# 03_ENET.net
KiCad netlist of a schematic drawn in Altium Designer
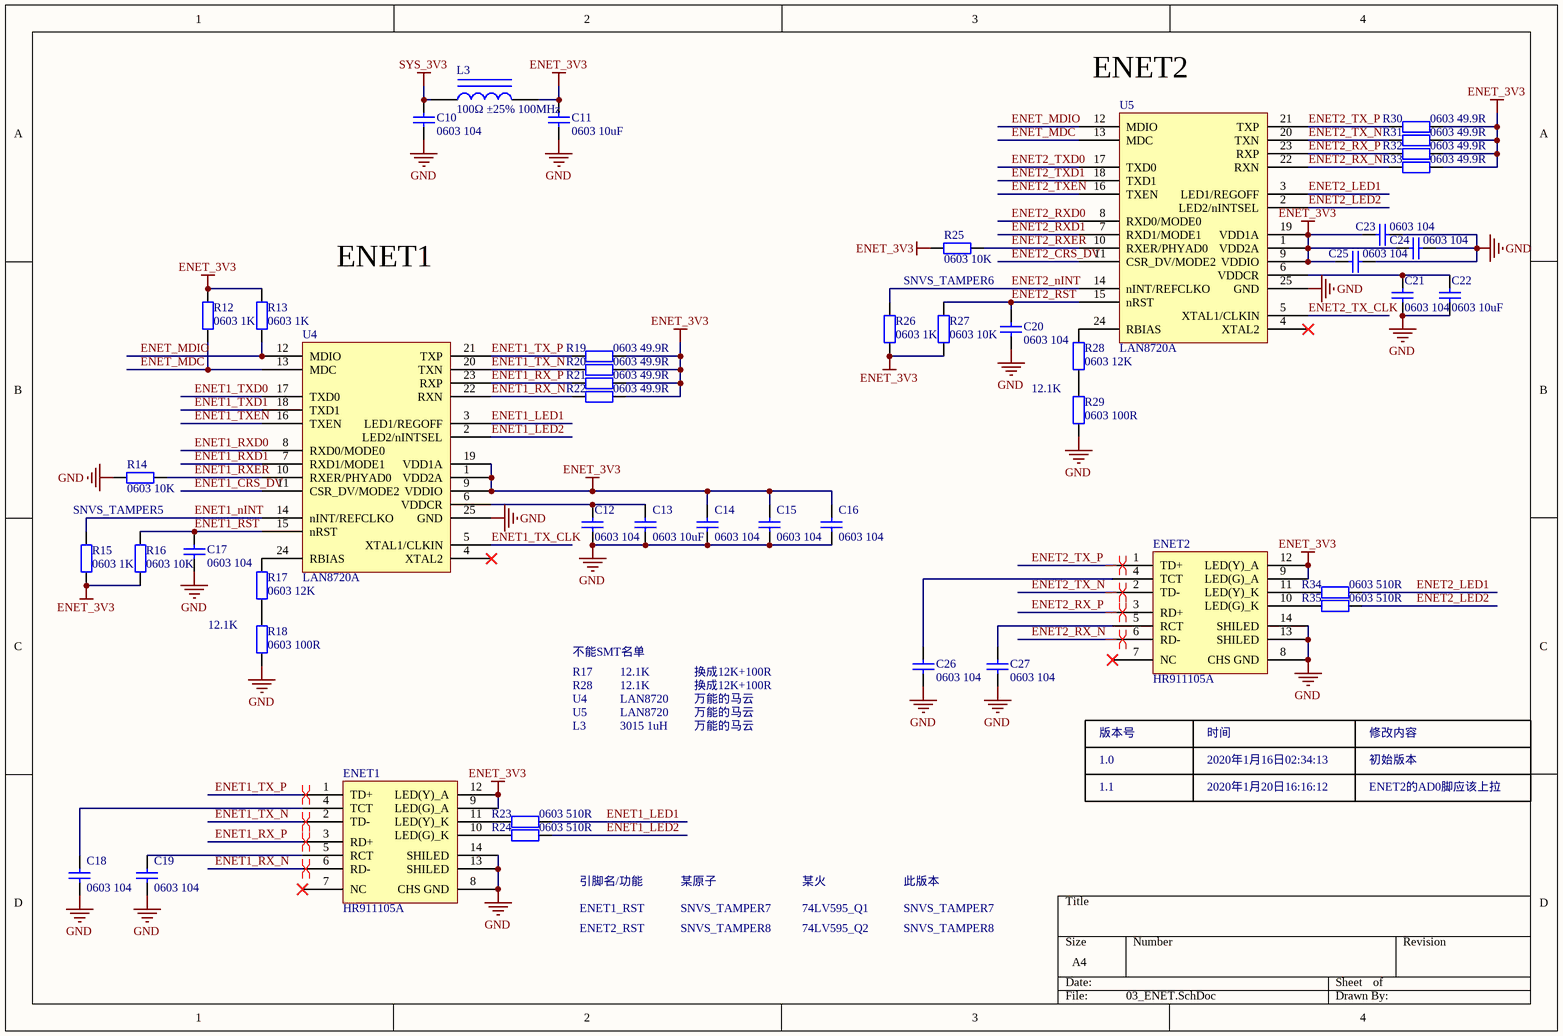
[diagram p0: 03_ENET.SchDoc]

(export (version "E")
  (design (tool "Eeschema 10.0.6"))
  (components
    (comp (ref "C10")
      (value "0603 104")
      (footprint "LC-0603_C")
      (description "贴片电容")
      (libsource (lib "JLC") (part "0603 1.5nF (152) 10% 50V"))
    )
    (comp (ref "C11")
      (value "0603 10uF")
      (footprint "LC-0603_C")
      (description "贴片电容")
      (libsource (lib "JLC") (part "0603 1.5nF (152) 10% 50V"))
    )
    (comp (ref "C12")
      (value "0603 104")
      (footprint "LC-0603_C")
      (description "贴片电容")
      (libsource (lib "JLC") (part "0603 1.5nF (152) 10% 50V"))
    )
    (comp (ref "C13")
      (value "0603 10uF")
      (footprint "LC-0603_C")
      (description "贴片电容")
      (libsource (lib "JLC") (part "0603 1.5nF (152) 10% 50V"))
    )
    (comp (ref "C14")
      (value "0603 104")
      (footprint "LC-0603_C")
      (description "贴片电容")
      (libsource (lib "JLC") (part "0603 1.5nF (152) 10% 50V"))
    )
    (comp (ref "C15")
      (value "0603 104")
      (footprint "LC-0603_C")
      (description "贴片电容")
      (libsource (lib "JLC") (part "0603 1.5nF (152) 10% 50V"))
    )
    (comp (ref "C16")
      (value "0603 104")
      (footprint "LC-0603_C")
      (description "贴片电容")
      (libsource (lib "JLC") (part "0603 1.5nF (152) 10% 50V"))
    )
    (comp (ref "C17")
      (value "0603 104")
      (footprint "LC-0603_C")
      (description "贴片电容")
      (libsource (lib "JLC") (part "0603 1.5nF (152) 10% 50V"))
    )
    (comp (ref "C18")
      (value "0603 104")
      (footprint "LC-0603_C")
      (description "贴片电容")
      (libsource (lib "JLC") (part "0603 1.5nF (152) 10% 50V"))
    )
    (comp (ref "C19")
      (value "0603 104")
      (footprint "LC-0603_C")
      (description "贴片电容")
      (libsource (lib "JLC") (part "0603 1.5nF (152) 10% 50V"))
    )
    (comp (ref "C20")
      (value "0603 104")
      (footprint "LC-0603_C")
      (description "贴片电容")
      (libsource (lib "JLC") (part "0603 1.5nF (152) 10% 50V"))
    )
    (comp (ref "C21")
      (value "0603 104")
      (footprint "LC-0603_C")
      (description "贴片电容")
      (libsource (lib "JLC") (part "0603 1.5nF (152) 10% 50V"))
    )
    (comp (ref "C22")
      (value "0603 10uF")
      (footprint "LC-0603_C")
      (description "贴片电容")
      (libsource (lib "JLC") (part "0603 1.5nF (152) 10% 50V"))
    )
    (comp (ref "C23")
      (value "0603 104")
      (footprint "LC-0603_C")
      (description "贴片电容")
      (libsource (lib "JLC") (part "0603 1.5nF (152) 10% 50V"))
    )
    (comp (ref "C24")
      (value "0603 104")
      (footprint "LC-0603_C")
      (description "贴片电容")
      (libsource (lib "JLC") (part "0603 1.5nF (152) 10% 50V"))
    )
    (comp (ref "C25")
      (value "0603 104")
      (footprint "LC-0603_C")
      (description "贴片电容")
      (libsource (lib "JLC") (part "0603 1.5nF (152) 10% 50V"))
    )
    (comp (ref "C26")
      (value "0603 104")
      (footprint "LC-0603_C")
      (description "贴片电容")
      (libsource (lib "JLC") (part "0603 1.5nF (152) 10% 50V"))
    )
    (comp (ref "C27")
      (value "0603 104")
      (footprint "LC-0603_C")
      (description "贴片电容")
      (libsource (lib "JLC") (part "0603 1.5nF (152) 10% 50V"))
    )
    (comp (ref "ENET1")
      (value "HR911105A")
      (footprint "HR911105A")
      (libsource (lib "Integrated_Library2") (part "HR911105A"))
    )
    (comp (ref "ENET2")
      (value "HR911105A")
      (footprint "HR911105A")
      (libsource (lib "Integrated_Library2") (part "HR911105A"))
    )
    (comp (ref "L3")
      (value "100Ω ±25% 100MHz")
      (footprint "LC-0805_L")
      (description "贴片磁珠")
      (libsource (lib "JLC") (part "0805 100Ω 25% 100MHz"))
    )
    (comp (ref "R12")
      (value "0603 1K")
      (footprint "LC-0603_R")
      (description "贴片电阻")
      (libsource (lib "") (part "0603 1.1KΩ (1101) 1%_1"))
    )
    (comp (ref "R13")
      (value "0603 1K")
      (footprint "LC-0603_R")
      (description "贴片电阻")
      (libsource (lib "") (part "0603 1.1KΩ (1101) 1%_1"))
    )
    (comp (ref "R14")
      (value "0603 10K")
      (footprint "LC-0603_R")
      (description "贴片电阻")
      (libsource (lib "JLC") (part "0603 1.1KΩ (1101) 1%"))
    )
    (comp (ref "R15")
      (value "0603 1K")
      (footprint "LC-0603_R")
      (description "贴片电阻")
      (libsource (lib "") (part "0603 1.1KΩ (1101) 1%_3"))
    )
    (comp (ref "R16")
      (value "0603 10K")
      (footprint "LC-0603_R")
      (description "贴片电阻")
      (libsource (lib "") (part "0603 1.1KΩ (1101) 1%_3"))
    )
    (comp (ref "R17")
      (value "0603 12K")
      (footprint "LC-0603_R")
      (description "贴片电阻")
      (libsource (lib "") (part "0603 1.1KΩ (1101) 1%_3"))
    )
    (comp (ref "R18")
      (value "0603 100R")
      (footprint "LC-0603_R")
      (description "贴片电阻")
      (libsource (lib "") (part "0603 1.1KΩ (1101) 1%_3"))
    )
    (comp (ref "R19")
      (value "0603 49.9R")
      (footprint "LC-0603_R")
      (description "贴片电阻")
      (libsource (lib "") (part "0603 1.1KΩ (1101) 1%_2"))
    )
    (comp (ref "R20")
      (value "0603 49.9R")
      (footprint "LC-0603_R")
      (description "贴片电阻")
      (libsource (lib "") (part "0603 1.1KΩ (1101) 1%_2"))
    )
    (comp (ref "R21")
      (value "0603 49.9R")
      (footprint "LC-0603_R")
      (description "贴片电阻")
      (libsource (lib "") (part "0603 1.1KΩ (1101) 1%_2"))
    )
    (comp (ref "R22")
      (value "0603 49.9R")
      (footprint "LC-0603_R")
      (description "贴片电阻")
      (libsource (lib "") (part "0603 1.1KΩ (1101) 1%_2"))
    )
    (comp (ref "R23")
      (value "0603 510R")
      (footprint "LC-0603_R")
      (description "贴片电阻")
      (libsource (lib "") (part "0603 1.1KΩ (1101) 1%_2"))
    )
    (comp (ref "R24")
      (value "0603 510R")
      (footprint "LC-0603_R")
      (description "贴片电阻")
      (libsource (lib "") (part "0603 1.1KΩ (1101) 1%_2"))
    )
    (comp (ref "R25")
      (value "0603 10K")
      (footprint "LC-0603_R")
      (description "贴片电阻")
      (libsource (lib "JLC") (part "0603 1.1KΩ (1101) 1%"))
    )
    (comp (ref "R26")
      (value "0603 1K")
      (footprint "LC-0603_R")
      (description "贴片电阻")
      (libsource (lib "") (part "0603 1.1KΩ (1101) 1%_3"))
    )
    (comp (ref "R27")
      (value "0603 10K")
      (footprint "LC-0603_R")
      (description "贴片电阻")
      (libsource (lib "") (part "0603 1.1KΩ (1101) 1%_3"))
    )
    (comp (ref "R28")
      (value "0603 12K")
      (footprint "LC-0603_R")
      (description "贴片电阻")
      (libsource (lib "") (part "0603 1.1KΩ (1101) 1%_3"))
    )
    (comp (ref "R29")
      (value "0603 100R")
      (footprint "LC-0603_R")
      (description "贴片电阻")
      (libsource (lib "") (part "0603 1.1KΩ (1101) 1%_3"))
    )
    (comp (ref "R30")
      (value "0603 49.9R")
      (footprint "LC-0603_R")
      (description "贴片电阻")
      (libsource (lib "") (part "0603 1.1KΩ (1101) 1%_2"))
    )
    (comp (ref "R31")
      (value "0603 49.9R")
      (footprint "LC-0603_R")
      (description "贴片电阻")
      (libsource (lib "") (part "0603 1.1KΩ (1101) 1%_2"))
    )
    (comp (ref "R32")
      (value "0603 49.9R")
      (footprint "LC-0603_R")
      (description "贴片电阻")
      (libsource (lib "") (part "0603 1.1KΩ (1101) 1%_2"))
    )
    (comp (ref "R33")
      (value "0603 49.9R")
      (footprint "LC-0603_R")
      (description "贴片电阻")
      (libsource (lib "") (part "0603 1.1KΩ (1101) 1%_2"))
    )
    (comp (ref "R34")
      (value "0603 510R")
      (footprint "LC-0603_R")
      (description "贴片电阻")
      (libsource (lib "") (part "0603 1.1KΩ (1101) 1%_2"))
    )
    (comp (ref "R35")
      (value "0603 510R")
      (footprint "LC-0603_R")
      (description "贴片电阻")
      (libsource (lib "") (part "0603 1.1KΩ (1101) 1%_2"))
    )
    (comp (ref "U4")
      (value "LAN8720A")
      (footprint "QFN-24_4x4x05P")
      (libsource (lib "Integrated_Library2") (part "LAN8720A"))
    )
    (comp (ref "U5")
      (value "LAN8720A")
      (footprint "QFN-24_4x4x05P")
      (libsource (lib "Integrated_Library2") (part "LAN8720A"))
    )
  )
  (nets
    (net (code "1") (name "/ENET1_CRS_DV") (class "Default")
      (node (ref "U4") (pin "11") (pinfunction "CSR_DV/MODE2_11") (pintype "passive"))
    )
    (net (code "2") (name "/ENET1_LED1") (class "Default")
      (node (ref "R23") (pin "2") (pinfunction "2_2") (pintype "passive"))
      (node (ref "U4") (pin "3") (pinfunction "LED1/REGOFF_3") (pintype "passive"))
    )
    (net (code "3") (name "/ENET1_LED2") (class "Default")
      (node (ref "R24") (pin "2") (pinfunction "2_2") (pintype "passive"))
      (node (ref "U4") (pin "2") (pinfunction "LED2/nINTSEL_2") (pintype "passive"))
    )
    (net (code "4") (name "/ENET1_RST") (class "Default")
      (node (ref "C17") (pin "2") (pinfunction "2_2") (pintype "passive"))
      (node (ref "R16") (pin "1") (pinfunction "1_1") (pintype "passive"))
      (node (ref "U4") (pin "15") (pinfunction "nRST_15") (pintype "passive"))
    )
    (net (code "5") (name "/ENET1_RXD0") (class "Default")
      (node (ref "U4") (pin "8") (pinfunction "RXD0/MODE0_8") (pintype "passive"))
    )
    (net (code "6") (name "/ENET1_RXD1") (class "Default")
      (node (ref "U4") (pin "7") (pinfunction "RXD1/MODE1_7") (pintype "passive"))
    )
    (net (code "7") (name "/ENET1_RXER") (class "Default")
      (node (ref "R14") (pin "1") (pinfunction "1_1") (pintype "passive"))
      (node (ref "U4") (pin "10") (pinfunction "RXER/PHYAD0_10") (pintype "passive"))
    )
    (net (code "8") (name "/ENET1_RX_N") (class "Default")
      (node (ref "ENET1") (pin "6") (pinfunction "RD-_6") (pintype "passive"))
      (node (ref "R22") (pin "1") (pinfunction "1_1") (pintype "passive"))
      (node (ref "U4") (pin "22") (pinfunction "RXN_22") (pintype "passive"))
    )
    (net (code "9") (name "/ENET1_RX_P") (class "Default")
      (node (ref "ENET1") (pin "3") (pinfunction "RD+_3") (pintype "passive"))
      (node (ref "R21") (pin "1") (pinfunction "1_1") (pintype "passive"))
      (node (ref "U4") (pin "23") (pinfunction "RXP_23") (pintype "passive"))
    )
    (net (code "10") (name "/ENET1_TXD0") (class "Default")
      (node (ref "U4") (pin "17") (pinfunction "TXD0_17") (pintype "passive"))
    )
    (net (code "11") (name "/ENET1_TXD1") (class "Default")
      (node (ref "U4") (pin "18") (pinfunction "TXD1_18") (pintype "passive"))
    )
    (net (code "12") (name "/ENET1_TXEN") (class "Default")
      (node (ref "U4") (pin "16") (pinfunction "TXEN_16") (pintype "passive"))
    )
    (net (code "13") (name "/ENET1_TX_CLK") (class "Default")
      (node (ref "U4") (pin "5") (pinfunction "XTAL1/CLKIN_5") (pintype "passive"))
    )
    (net (code "14") (name "/ENET1_TX_N") (class "Default")
      (node (ref "ENET1") (pin "2") (pinfunction "TD-_2") (pintype "passive"))
      (node (ref "R20") (pin "1") (pinfunction "1_1") (pintype "passive"))
      (node (ref "U4") (pin "20") (pinfunction "TXN_20") (pintype "passive"))
    )
    (net (code "15") (name "/ENET1_TX_P") (class "Default")
      (node (ref "ENET1") (pin "1") (pinfunction "TD+_1") (pintype "passive"))
      (node (ref "R19") (pin "1") (pinfunction "1_1") (pintype "passive"))
      (node (ref "U4") (pin "21") (pinfunction "TXP_21") (pintype "passive"))
    )
    (net (code "16") (name "/ENET1_nINT") (class "Default")
      (node (ref "R15") (pin "1") (pinfunction "1_1") (pintype "passive"))
      (node (ref "U4") (pin "14") (pinfunction "nINT/REFCLKO_14") (pintype "passive"))
    )
    (net (code "17") (name "/ENET2_CRS_DV") (class "Default")
      (node (ref "U5") (pin "11") (pinfunction "CSR_DV/MODE2_11") (pintype "passive"))
    )
    (net (code "18") (name "/ENET2_LED1") (class "Default")
      (node (ref "R34") (pin "2") (pinfunction "2_2") (pintype "passive"))
      (node (ref "U5") (pin "3") (pinfunction "LED1/REGOFF_3") (pintype "passive"))
    )
    (net (code "19") (name "/ENET2_LED2") (class "Default")
      (node (ref "R35") (pin "2") (pinfunction "2_2") (pintype "passive"))
      (node (ref "U5") (pin "2") (pinfunction "LED2/nINTSEL_2") (pintype "passive"))
    )
    (net (code "20") (name "/ENET2_RST") (class "Default")
      (node (ref "C20") (pin "2") (pinfunction "2_2") (pintype "passive"))
      (node (ref "R27") (pin "1") (pinfunction "1_1") (pintype "passive"))
      (node (ref "U5") (pin "15") (pinfunction "nRST_15") (pintype "passive"))
    )
    (net (code "21") (name "/ENET2_RXD0") (class "Default")
      (node (ref "U5") (pin "8") (pinfunction "RXD0/MODE0_8") (pintype "passive"))
    )
    (net (code "22") (name "/ENET2_RXD1") (class "Default")
      (node (ref "U5") (pin "7") (pinfunction "RXD1/MODE1_7") (pintype "passive"))
    )
    (net (code "23") (name "/ENET2_RXER") (class "Default")
      (node (ref "R25") (pin "1") (pinfunction "1_1") (pintype "passive"))
      (node (ref "U5") (pin "10") (pinfunction "RXER/PHYAD0_10") (pintype "passive"))
    )
    (net (code "24") (name "/ENET2_RX_N") (class "Default")
      (node (ref "ENET2") (pin "6") (pinfunction "RD-_6") (pintype "passive"))
      (node (ref "R33") (pin "1") (pinfunction "1_1") (pintype "passive"))
      (node (ref "U5") (pin "22") (pinfunction "RXN_22") (pintype "passive"))
    )
    (net (code "25") (name "/ENET2_RX_P") (class "Default")
      (node (ref "ENET2") (pin "3") (pinfunction "RD+_3") (pintype "passive"))
      (node (ref "R32") (pin "1") (pinfunction "1_1") (pintype "passive"))
      (node (ref "U5") (pin "23") (pinfunction "RXP_23") (pintype "passive"))
    )
    (net (code "26") (name "/ENET2_TXD0") (class "Default")
      (node (ref "U5") (pin "17") (pinfunction "TXD0_17") (pintype "passive"))
    )
    (net (code "27") (name "/ENET2_TXD1") (class "Default")
      (node (ref "U5") (pin "18") (pinfunction "TXD1_18") (pintype "passive"))
    )
    (net (code "28") (name "/ENET2_TXEN") (class "Default")
      (node (ref "U5") (pin "16") (pinfunction "TXEN_16") (pintype "passive"))
    )
    (net (code "29") (name "/ENET2_TX_CLK") (class "Default")
      (node (ref "U5") (pin "5") (pinfunction "XTAL1/CLKIN_5") (pintype "passive"))
    )
    (net (code "30") (name "/ENET2_TX_N") (class "Default")
      (node (ref "ENET2") (pin "2") (pinfunction "TD-_2") (pintype "passive"))
      (node (ref "R31") (pin "1") (pinfunction "1_1") (pintype "passive"))
      (node (ref "U5") (pin "20") (pinfunction "TXN_20") (pintype "passive"))
    )
    (net (code "31") (name "/ENET2_TX_P") (class "Default")
      (node (ref "ENET2") (pin "1") (pinfunction "TD+_1") (pintype "passive"))
      (node (ref "R30") (pin "1") (pinfunction "1_1") (pintype "passive"))
      (node (ref "U5") (pin "21") (pinfunction "TXP_21") (pintype "passive"))
    )
    (net (code "32") (name "/ENET2_nINT") (class "Default")
      (node (ref "R26") (pin "1") (pinfunction "1_1") (pintype "passive"))
      (node (ref "U5") (pin "14") (pinfunction "nINT/REFCLKO_14") (pintype "passive"))
    )
    (net (code "33") (name "/ENET_MDC") (class "Default")
      (node (ref "R12") (pin "1") (pinfunction "1_1") (pintype "passive"))
      (node (ref "U4") (pin "13") (pinfunction "MDC_13") (pintype "passive"))
      (node (ref "U5") (pin "13") (pinfunction "MDC_13") (pintype "passive"))
    )
    (net (code "34") (name "/ENET_MDIO") (class "Default")
      (node (ref "R13") (pin "1") (pinfunction "1_1") (pintype "passive"))
      (node (ref "U4") (pin "12") (pinfunction "MDIO_12") (pintype "passive"))
      (node (ref "U5") (pin "12") (pinfunction "MDIO_12") (pintype "passive"))
    )
    (net (code "35") (name "ENET_3V3") (class "Default")
      (node (ref "C11") (pin "2") (pinfunction "2_2") (pintype "passive"))
      (node (ref "C14") (pin "2") (pinfunction "2_2") (pintype "passive"))
      (node (ref "C15") (pin "2") (pinfunction "2_2") (pintype "passive"))
      (node (ref "C16") (pin "2") (pinfunction "2_2") (pintype "passive"))
      (node (ref "C23") (pin "2") (pinfunction "2_2") (pintype "passive"))
      (node (ref "C24") (pin "2") (pinfunction "2_2") (pintype "passive"))
      (node (ref "C25") (pin "2") (pinfunction "2_2") (pintype "passive"))
      (node (ref "ENET1") (pin "12") (pinfunction "LED(Y)_A_12") (pintype "passive"))
      (node (ref "ENET1") (pin "9") (pinfunction "LED(G)_A_9") (pintype "passive"))
      (node (ref "ENET2") (pin "12") (pinfunction "LED(Y)_A_12") (pintype "passive"))
      (node (ref "ENET2") (pin "9") (pinfunction "LED(G)_A_9") (pintype "passive"))
      (node (ref "L3") (pin "2") (pinfunction "2_2") (pintype "passive"))
      (node (ref "R12") (pin "2") (pinfunction "2_2") (pintype "passive"))
      (node (ref "R13") (pin "2") (pinfunction "2_2") (pintype "passive"))
      (node (ref "R15") (pin "2") (pinfunction "2_2") (pintype "passive"))
      (node (ref "R16") (pin "2") (pinfunction "2_2") (pintype "passive"))
      (node (ref "R19") (pin "2") (pinfunction "2_2") (pintype "passive"))
      (node (ref "R20") (pin "2") (pinfunction "2_2") (pintype "passive"))
      (node (ref "R21") (pin "2") (pinfunction "2_2") (pintype "passive"))
      (node (ref "R22") (pin "2") (pinfunction "2_2") (pintype "passive"))
      (node (ref "R25") (pin "2") (pinfunction "2_2") (pintype "passive"))
      (node (ref "R26") (pin "2") (pinfunction "2_2") (pintype "passive"))
      (node (ref "R27") (pin "2") (pinfunction "2_2") (pintype "passive"))
      (node (ref "R30") (pin "2") (pinfunction "2_2") (pintype "passive"))
      (node (ref "R31") (pin "2") (pinfunction "2_2") (pintype "passive"))
      (node (ref "R32") (pin "2") (pinfunction "2_2") (pintype "passive"))
      (node (ref "R33") (pin "2") (pinfunction "2_2") (pintype "passive"))
      (node (ref "U4") (pin "1") (pinfunction "VDD2A_1") (pintype "passive"))
      (node (ref "U4") (pin "19") (pinfunction "VDD1A_19") (pintype "passive"))
      (node (ref "U4") (pin "9") (pinfunction "VDDIO_9") (pintype "passive"))
      (node (ref "U5") (pin "1") (pinfunction "VDD2A_1") (pintype "passive"))
      (node (ref "U5") (pin "19") (pinfunction "VDD1A_19") (pintype "passive"))
      (node (ref "U5") (pin "9") (pinfunction "VDDIO_9") (pintype "passive"))
    )
    (net (code "36") (name "GND") (class "Default")
      (node (ref "C10") (pin "1") (pinfunction "1_1") (pintype "passive"))
      (node (ref "C11") (pin "1") (pinfunction "1_1") (pintype "passive"))
      (node (ref "C12") (pin "1") (pinfunction "1_1") (pintype "passive"))
      (node (ref "C13") (pin "1") (pinfunction "1_1") (pintype "passive"))
      (node (ref "C14") (pin "1") (pinfunction "1_1") (pintype "passive"))
      (node (ref "C15") (pin "1") (pinfunction "1_1") (pintype "passive"))
      (node (ref "C16") (pin "1") (pinfunction "1_1") (pintype "passive"))
      (node (ref "C17") (pin "1") (pinfunction "1_1") (pintype "passive"))
      (node (ref "C18") (pin "1") (pinfunction "1_1") (pintype "passive"))
      (node (ref "C19") (pin "1") (pinfunction "1_1") (pintype "passive"))
      (node (ref "C20") (pin "1") (pinfunction "1_1") (pintype "passive"))
      (node (ref "C21") (pin "1") (pinfunction "1_1") (pintype "passive"))
      (node (ref "C22") (pin "1") (pinfunction "1_1") (pintype "passive"))
      (node (ref "C23") (pin "1") (pinfunction "1_1") (pintype "passive"))
      (node (ref "C24") (pin "1") (pinfunction "1_1") (pintype "passive"))
      (node (ref "C25") (pin "1") (pinfunction "1_1") (pintype "passive"))
      (node (ref "C26") (pin "2") (pinfunction "2_2") (pintype "passive"))
      (node (ref "C27") (pin "2") (pinfunction "2_2") (pintype "passive"))
      (node (ref "ENET1") (pin "13") (pinfunction "SHILED_13") (pintype "passive"))
      (node (ref "ENET1") (pin "14") (pinfunction "SHILED_14") (pintype "passive"))
      (node (ref "ENET1") (pin "8") (pinfunction "CHS_GND_8") (pintype "passive"))
      (node (ref "ENET2") (pin "13") (pinfunction "SHILED_13") (pintype "passive"))
      (node (ref "ENET2") (pin "14") (pinfunction "SHILED_14") (pintype "passive"))
      (node (ref "ENET2") (pin "8") (pinfunction "CHS_GND_8") (pintype "passive"))
      (node (ref "R14") (pin "2") (pinfunction "2_2") (pintype "passive"))
      (node (ref "R18") (pin "2") (pinfunction "2_2") (pintype "passive"))
      (node (ref "R29") (pin "2") (pinfunction "2_2") (pintype "passive"))
      (node (ref "U4") (pin "25") (pinfunction "GND_25") (pintype "passive"))
      (node (ref "U5") (pin "25") (pinfunction "GND_25") (pintype "passive"))
    )
    (net (code "37") (name "Net-(ENET1-LED(G)_K)") (class "Default")
      (node (ref "ENET1") (pin "10") (pinfunction "LED(G)_K_10") (pintype "passive"))
      (node (ref "R24") (pin "1") (pinfunction "1_1") (pintype "passive"))
    )
    (net (code "38") (name "Net-(ENET1-LED(Y)_K)") (class "Default")
      (node (ref "ENET1") (pin "11") (pinfunction "LED(Y)_K_11") (pintype "passive"))
      (node (ref "R23") (pin "1") (pinfunction "1_1") (pintype "passive"))
    )
    (net (code "39") (name "Net-(ENET1-RCT)") (class "Default")
      (node (ref "C19") (pin "2") (pinfunction "2_2") (pintype "passive"))
      (node (ref "ENET1") (pin "5") (pinfunction "RCT_5") (pintype "passive"))
    )
    (net (code "40") (name "Net-(ENET1-TCT)") (class "Default")
      (node (ref "C18") (pin "2") (pinfunction "2_2") (pintype "passive"))
      (node (ref "ENET1") (pin "4") (pinfunction "TCT_4") (pintype "passive"))
    )
    (net (code "41") (name "Net-(ENET2-LED(G)_K)") (class "Default")
      (node (ref "ENET2") (pin "10") (pinfunction "LED(G)_K_10") (pintype "passive"))
      (node (ref "R35") (pin "1") (pinfunction "1_1") (pintype "passive"))
    )
    (net (code "42") (name "Net-(ENET2-LED(Y)_K)") (class "Default")
      (node (ref "ENET2") (pin "11") (pinfunction "LED(Y)_K_11") (pintype "passive"))
      (node (ref "R34") (pin "1") (pinfunction "1_1") (pintype "passive"))
    )
    (net (code "43") (name "Net-(ENET2-RCT)") (class "Default")
      (node (ref "C27") (pin "1") (pinfunction "1_1") (pintype "passive"))
      (node (ref "ENET2") (pin "5") (pinfunction "RCT_5") (pintype "passive"))
    )
    (net (code "44") (name "Net-(ENET2-TCT)") (class "Default")
      (node (ref "C26") (pin "1") (pinfunction "1_1") (pintype "passive"))
      (node (ref "ENET2") (pin "4") (pinfunction "TCT_4") (pintype "passive"))
    )
    (net (code "45") (name "Net-(R17-Pad2)") (class "Default")
      (node (ref "R17") (pin "2") (pinfunction "2_2") (pintype "passive"))
      (node (ref "R18") (pin "1") (pinfunction "1_1") (pintype "passive"))
    )
    (net (code "46") (name "Net-(R28-Pad2)") (class "Default")
      (node (ref "R28") (pin "2") (pinfunction "2_2") (pintype "passive"))
      (node (ref "R29") (pin "1") (pinfunction "1_1") (pintype "passive"))
    )
    (net (code "47") (name "Net-(U4-RBIAS)") (class "Default")
      (node (ref "R17") (pin "1") (pinfunction "1_1") (pintype "passive"))
      (node (ref "U4") (pin "24") (pinfunction "RBIAS_24") (pintype "passive"))
    )
    (net (code "48") (name "Net-(U4-VDDCR)") (class "Default")
      (node (ref "C12") (pin "2") (pinfunction "2_2") (pintype "passive"))
      (node (ref "C13") (pin "2") (pinfunction "2_2") (pintype "passive"))
      (node (ref "U4") (pin "6") (pinfunction "VDDCR_6") (pintype "passive"))
    )
    (net (code "49") (name "Net-(U5-RBIAS)") (class "Default")
      (node (ref "R28") (pin "1") (pinfunction "1_1") (pintype "passive"))
      (node (ref "U5") (pin "24") (pinfunction "RBIAS_24") (pintype "passive"))
    )
    (net (code "50") (name "Net-(U5-VDDCR)") (class "Default")
      (node (ref "C21") (pin "2") (pinfunction "2_2") (pintype "passive"))
      (node (ref "C22") (pin "2") (pinfunction "2_2") (pintype "passive"))
      (node (ref "U5") (pin "6") (pinfunction "VDDCR_6") (pintype "passive"))
    )
    (net (code "51") (name "SYS_3V3") (class "Default")
      (node (ref "C10") (pin "2") (pinfunction "2_2") (pintype "passive"))
      (node (ref "L3") (pin "1") (pinfunction "1_1") (pintype "passive"))
    )
    (net (code "52") (name "unconnected-(ENET1-NC-Pad7)") (class "Default")
      (node (ref "ENET1") (pin "7") (pinfunction "NC_7") (pintype "passive+no_connect"))
    )
    (net (code "53") (name "unconnected-(ENET2-NC-Pad7)") (class "Default")
      (node (ref "ENET2") (pin "7") (pinfunction "NC_7") (pintype "passive+no_connect"))
    )
    (net (code "54") (name "unconnected-(U4-XTAL2-Pad4)") (class "Default")
      (node (ref "U4") (pin "4") (pinfunction "XTAL2_4") (pintype "passive+no_connect"))
    )
    (net (code "55") (name "unconnected-(U5-XTAL2-Pad4)") (class "Default")
      (node (ref "U5") (pin "4") (pinfunction "XTAL2_4") (pintype "passive+no_connect"))
    )
  )
)
